# SSB_Transceiver_Digital.net
KiCad netlist of a schematic drawn in EAGLE
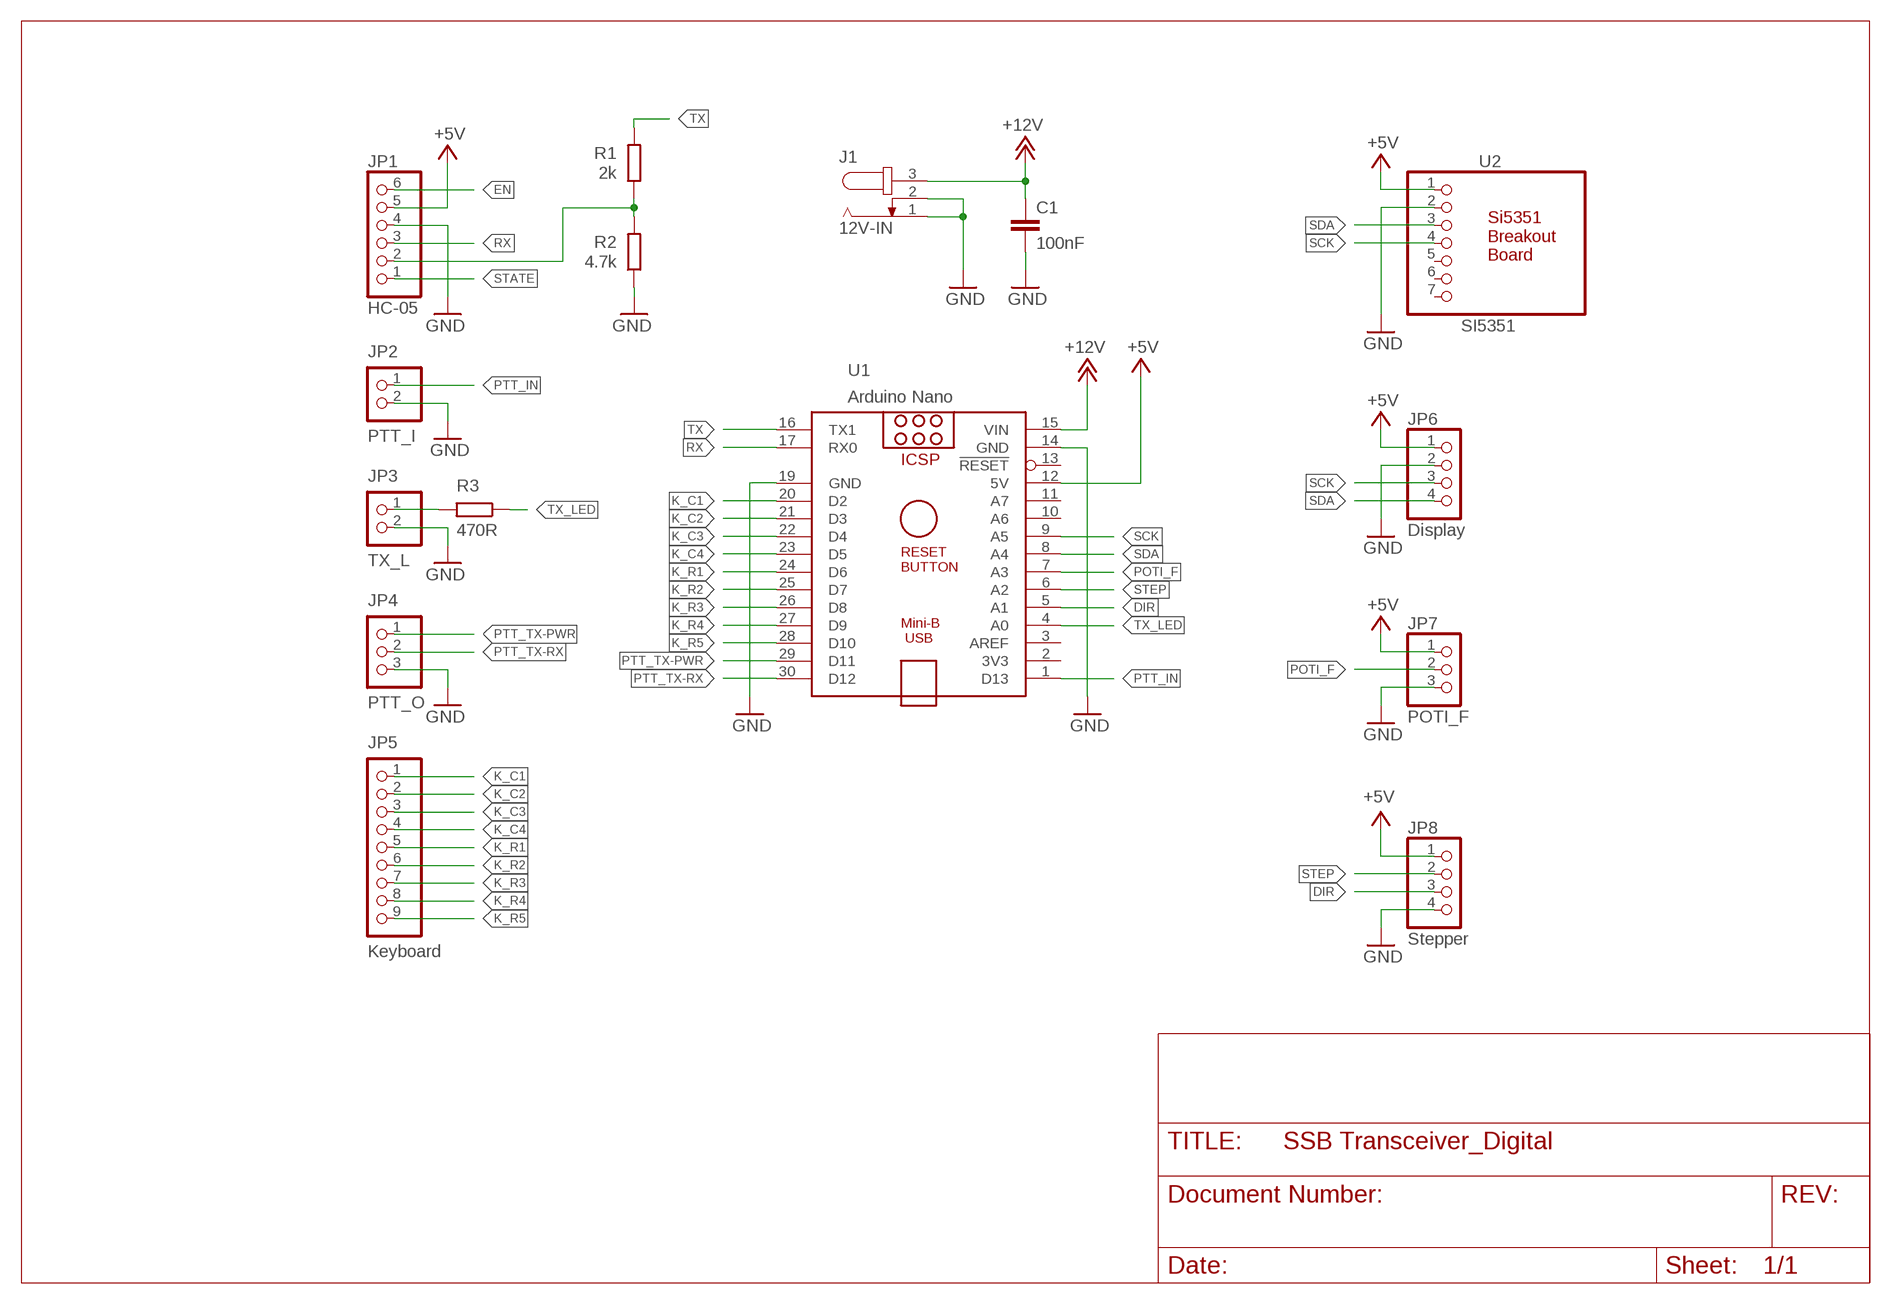
[diagram p0: schematic, sheet 1]

(export (version "E")
  (design (tool "Eeschema 10.0.6"))
  (components
    (comp (ref "C1")
      (value "100nF")
      (footprint "eagle-import:C0805K")
      (libsource (lib "eagle-import") (part "C-EUC0805K"))
    )
    (comp (ref "J1")
      (value "12V-IN")
      (footprint "eagle-import:SPC4078")
      (libsource (lib "eagle-import") (part "JACK-PLUG1"))
    )
    (comp (ref "JP1")
      (value "HC-05")
      (footprint "eagle-import:1X06")
      (libsource (lib "eagle-import") (part "PINHD-1X6"))
    )
    (comp (ref "JP2")
      (value "PTT_I")
      (footprint "eagle-import:1X02")
      (libsource (lib "eagle-import") (part "PINHD-1X2"))
    )
    (comp (ref "JP3")
      (value "TX_L")
      (footprint "eagle-import:1X02")
      (libsource (lib "eagle-import") (part "PINHD-1X2"))
    )
    (comp (ref "JP4")
      (value "PTT_O")
      (footprint "eagle-import:1X03")
      (libsource (lib "eagle-import") (part "PINHD-1X3"))
    )
    (comp (ref "JP5")
      (value "Keyboard")
      (footprint "eagle-import:1X09")
      (libsource (lib "eagle-import") (part "PINHD-1X9"))
    )
    (comp (ref "JP6")
      (value "Display")
      (footprint "eagle-import:1X04")
      (libsource (lib "eagle-import") (part "PINHD-1X4"))
    )
    (comp (ref "JP7")
      (value "POTI_F")
      (footprint "eagle-import:1X03")
      (libsource (lib "eagle-import") (part "PINHD-1X3"))
    )
    (comp (ref "JP8")
      (value "Stepper")
      (footprint "eagle-import:1X04")
      (libsource (lib "eagle-import") (part "PINHD-1X4"))
    )
    (comp (ref "R1")
      (value "2k")
      (footprint "eagle-import:R0805")
      (libsource (lib "eagle-import") (part "R-EU_R0805"))
    )
    (comp (ref "R2")
      (value "4.7k")
      (footprint "eagle-import:R0805")
      (libsource (lib "eagle-import") (part "R-EU_R0805"))
    )
    (comp (ref "R3")
      (value "470R")
      (footprint "eagle-import:R0805")
      (libsource (lib "eagle-import") (part "R-EU_R0805"))
    )
    (comp (ref "U1")
      (value "Arduino Nano")
      (footprint "eagle-import:ARDUINO_NANO")
      (libsource (lib "eagle-import") (part "ARDUINO_NANO"))
    )
    (comp (ref "U2")
      (value "SI5351")
      (footprint "eagle-import:1X07")
      (libsource (lib "eagle-import") (part "SI5351"))
    )
  )
  (nets
    (net (code "1") (name "+5V") (class "Default")
      (node (ref "JP1") (pin "5") (pinfunction "5_5") (pintype "passive"))
      (node (ref "JP6") (pin "1") (pinfunction "1_1") (pintype "passive"))
      (node (ref "JP7") (pin "1") (pinfunction "1_1") (pintype "passive"))
      (node (ref "JP8") (pin "1") (pinfunction "1_1") (pintype "passive"))
      (node (ref "U1") (pin "12") (pinfunction "5V_12") (pintype "power_in"))
      (node (ref "U2") (pin "1") (pinfunction "1_1") (pintype "passive"))
    )
    (net (code "2") (name "+12V") (class "Default")
      (node (ref "C1") (pin "1") (pinfunction "1_1") (pintype "passive"))
      (node (ref "J1") (pin "3") (pinfunction "3_3") (pintype "passive"))
      (node (ref "U1") (pin "15") (pinfunction "VIN_15") (pintype "power_in"))
    )
    (net (code "3") (name "DIR") (class "Default")
      (node (ref "JP8") (pin "3") (pinfunction "3_3") (pintype "passive"))
      (node (ref "U1") (pin "5") (pinfunction "A1_5") (pintype "bidirectional"))
    )
    (net (code "4") (name "EN") (class "Default")
      (node (ref "JP1") (pin "6") (pinfunction "6_6") (pintype "passive"))
    )
    (net (code "5") (name "GND") (class "Default")
      (node (ref "C1") (pin "2") (pinfunction "2_2") (pintype "passive"))
      (node (ref "J1") (pin "1") (pinfunction "1_1") (pintype "passive"))
      (node (ref "J1") (pin "2") (pinfunction "2_2") (pintype "passive"))
      (node (ref "JP1") (pin "4") (pinfunction "4_4") (pintype "passive"))
      (node (ref "JP2") (pin "2") (pinfunction "2_2") (pintype "passive"))
      (node (ref "JP3") (pin "2") (pinfunction "2_2") (pintype "passive"))
      (node (ref "JP4") (pin "3") (pinfunction "3_3") (pintype "passive"))
      (node (ref "JP6") (pin "2") (pinfunction "2_2") (pintype "passive"))
      (node (ref "JP7") (pin "3") (pinfunction "3_3") (pintype "passive"))
      (node (ref "JP8") (pin "4") (pinfunction "4_4") (pintype "passive"))
      (node (ref "R2") (pin "1") (pinfunction "1_1") (pintype "passive"))
      (node (ref "U1") (pin "14") (pinfunction "GND_14") (pintype "power_in"))
      (node (ref "U1") (pin "19") (pinfunction "GND_19") (pintype "power_in"))
      (node (ref "U2") (pin "2") (pinfunction "2_2") (pintype "passive"))
    )
    (net (code "6") (name "K_C1") (class "Default")
      (node (ref "JP5") (pin "1") (pinfunction "1_1") (pintype "passive"))
      (node (ref "U1") (pin "20") (pinfunction "D2_20") (pintype "bidirectional"))
    )
    (net (code "7") (name "K_C2") (class "Default")
      (node (ref "JP5") (pin "2") (pinfunction "2_2") (pintype "passive"))
      (node (ref "U1") (pin "21") (pinfunction "D3_21") (pintype "bidirectional"))
    )
    (net (code "8") (name "K_C3") (class "Default")
      (node (ref "JP5") (pin "3") (pinfunction "3_3") (pintype "passive"))
      (node (ref "U1") (pin "22") (pinfunction "D4_22") (pintype "bidirectional"))
    )
    (net (code "9") (name "K_C4") (class "Default")
      (node (ref "JP5") (pin "4") (pinfunction "4_4") (pintype "passive"))
      (node (ref "U1") (pin "23") (pinfunction "D5_23") (pintype "bidirectional"))
    )
    (net (code "10") (name "K_R1") (class "Default")
      (node (ref "JP5") (pin "5") (pinfunction "5_5") (pintype "passive"))
      (node (ref "U1") (pin "24") (pinfunction "D6_24") (pintype "bidirectional"))
    )
    (net (code "11") (name "K_R2") (class "Default")
      (node (ref "JP5") (pin "6") (pinfunction "6_6") (pintype "passive"))
      (node (ref "U1") (pin "25") (pinfunction "D7_25") (pintype "bidirectional"))
    )
    (net (code "12") (name "K_R3") (class "Default")
      (node (ref "JP5") (pin "7") (pinfunction "7_7") (pintype "passive"))
      (node (ref "U1") (pin "26") (pinfunction "D8_26") (pintype "bidirectional"))
    )
    (net (code "13") (name "K_R4") (class "Default")
      (node (ref "JP5") (pin "8") (pinfunction "8_8") (pintype "passive"))
      (node (ref "U1") (pin "27") (pinfunction "D9_27") (pintype "bidirectional"))
    )
    (net (code "14") (name "K_R5") (class "Default")
      (node (ref "JP5") (pin "9") (pinfunction "9_9") (pintype "passive"))
      (node (ref "U1") (pin "28") (pinfunction "D10_28") (pintype "bidirectional"))
    )
    (net (code "15") (name "Net-(JP1-Pad2)") (class "Default")
      (node (ref "JP1") (pin "2") (pinfunction "2_2") (pintype "passive"))
      (node (ref "R1") (pin "1") (pinfunction "1_1") (pintype "passive"))
      (node (ref "R2") (pin "2") (pinfunction "2_2") (pintype "passive"))
    )
    (net (code "16") (name "Net-(JP3-Pad1)") (class "Default")
      (node (ref "JP3") (pin "1") (pinfunction "1_1") (pintype "passive"))
      (node (ref "R3") (pin "2") (pinfunction "2_2") (pintype "passive"))
    )
    (net (code "17") (name "POTI_F") (class "Default")
      (node (ref "JP7") (pin "2") (pinfunction "2_2") (pintype "passive"))
      (node (ref "U1") (pin "7") (pinfunction "A3_7") (pintype "bidirectional"))
    )
    (net (code "18") (name "PTT_IN") (class "Default")
      (node (ref "JP2") (pin "1") (pinfunction "1_1") (pintype "passive"))
      (node (ref "U1") (pin "1") (pinfunction "D13_1") (pintype "bidirectional"))
    )
    (net (code "19") (name "PTT_TX-PWR") (class "Default")
      (node (ref "JP4") (pin "1") (pinfunction "1_1") (pintype "passive"))
      (node (ref "U1") (pin "29") (pinfunction "D11_29") (pintype "bidirectional"))
    )
    (net (code "20") (name "PTT_TX-RX") (class "Default")
      (node (ref "JP4") (pin "2") (pinfunction "2_2") (pintype "passive"))
      (node (ref "U1") (pin "30") (pinfunction "D12_30") (pintype "bidirectional"))
    )
    (net (code "21") (name "RX") (class "Default")
      (node (ref "JP1") (pin "3") (pinfunction "3_3") (pintype "passive"))
      (node (ref "U1") (pin "17") (pinfunction "RX0_17") (pintype "bidirectional"))
    )
    (net (code "22") (name "SCK") (class "Default")
      (node (ref "JP6") (pin "3") (pinfunction "3_3") (pintype "passive"))
      (node (ref "U1") (pin "9") (pinfunction "A5_9") (pintype "bidirectional"))
      (node (ref "U2") (pin "4") (pinfunction "4_4") (pintype "passive"))
    )
    (net (code "23") (name "SDA") (class "Default")
      (node (ref "JP6") (pin "4") (pinfunction "4_4") (pintype "passive"))
      (node (ref "U1") (pin "8") (pinfunction "A4_8") (pintype "bidirectional"))
      (node (ref "U2") (pin "3") (pinfunction "3_3") (pintype "passive"))
    )
    (net (code "24") (name "STATE") (class "Default")
      (node (ref "JP1") (pin "1") (pinfunction "1_1") (pintype "passive"))
    )
    (net (code "25") (name "STEP") (class "Default")
      (node (ref "JP8") (pin "2") (pinfunction "2_2") (pintype "passive"))
      (node (ref "U1") (pin "6") (pinfunction "A2_6") (pintype "bidirectional"))
    )
    (net (code "26") (name "TX") (class "Default")
      (node (ref "R1") (pin "2") (pinfunction "2_2") (pintype "passive"))
      (node (ref "U1") (pin "16") (pinfunction "TX1_16") (pintype "bidirectional"))
    )
    (net (code "27") (name "TX_LED") (class "Default")
      (node (ref "R3") (pin "1") (pinfunction "1_1") (pintype "passive"))
      (node (ref "U1") (pin "4") (pinfunction "A0_4") (pintype "bidirectional"))
    )
    (net (code "28") (name "unconnected-(U1-3V3-Pad2)") (class "Default")
      (node (ref "U1") (pin "2") (pinfunction "3V3_2") (pintype "output"))
    )
    (net (code "29") (name "unconnected-(U1-A6-Pad10)") (class "Default")
      (node (ref "U1") (pin "10") (pinfunction "A6_10") (pintype "bidirectional"))
    )
    (net (code "30") (name "unconnected-(U1-A7-Pad11)") (class "Default")
      (node (ref "U1") (pin "11") (pinfunction "A7_11") (pintype "bidirectional"))
    )
    (net (code "31") (name "unconnected-(U1-AREF-Pad3)") (class "Default")
      (node (ref "U1") (pin "3") (pinfunction "AREF_3") (pintype "input"))
    )
    (net (code "32") (name "unconnected-(U1-~{RESET}-Pad13)") (class "Default")
      (node (ref "U1") (pin "13") (pinfunction "~{RESET}_13") (pintype "input"))
    )
    (net (code "33") (name "unconnected-(U2-Pad5)") (class "Default")
      (node (ref "U2") (pin "5") (pinfunction "5_5") (pintype "passive"))
    )
    (net (code "34") (name "unconnected-(U2-Pad6)") (class "Default")
      (node (ref "U2") (pin "6") (pinfunction "6_6") (pintype "passive"))
    )
    (net (code "35") (name "unconnected-(U2-Pad7)") (class "Default")
      (node (ref "U2") (pin "7") (pinfunction "7_7") (pintype "passive"))
    )
  )
)
